# INA128.net
KiCad netlist of a schematic drawn in Altium Designer
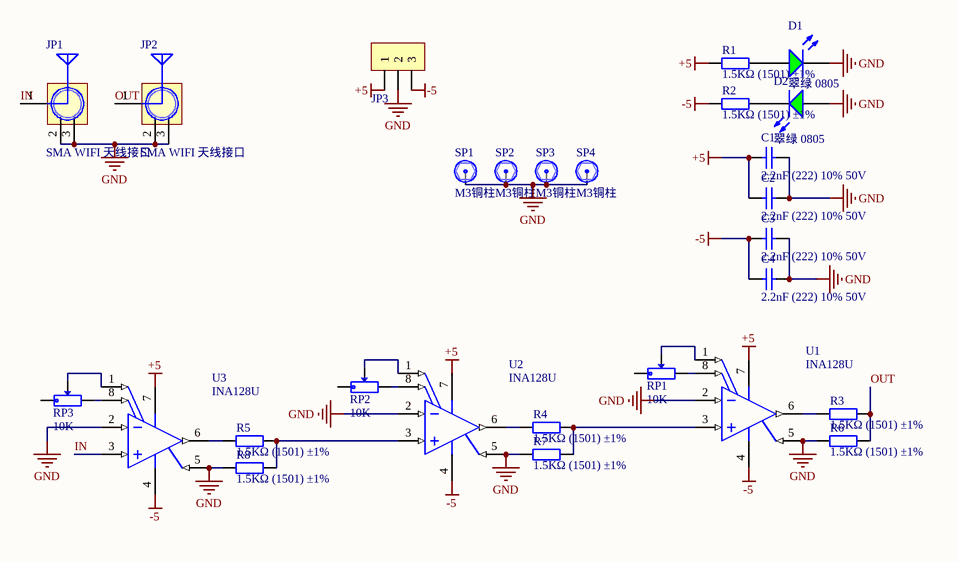
[diagram p0: INA128仪放.SchDoc]

(export (version "E")
  (design (tool "Eeschema 10.0.6"))
  (components
    (comp (ref "C1")
      (value "2.2nF (222) 10% 50V")
      (footprint "0603_C")
      (description "贴片电容")
      (libsource (lib "Miscellaneous Devices LC") (part "0603 2.2nF (222) 10% 50V"))
    )
    (comp (ref "C2")
      (value "2.2nF (222) 10% 50V")
      (footprint "0603_C")
      (description "贴片电容")
      (libsource (lib "Miscellaneous Devices LC") (part "0603 2.2nF (222) 10% 50V"))
    )
    (comp (ref "C3")
      (value "2.2nF (222) 10% 50V")
      (footprint "0603_C")
      (description "贴片电容")
      (libsource (lib "Miscellaneous Devices LC") (part "0603 2.2nF (222) 10% 50V"))
    )
    (comp (ref "C4")
      (value "2.2nF (222) 10% 50V")
      (footprint "0603_C")
      (description "贴片电容")
      (libsource (lib "Miscellaneous Devices LC") (part "0603 2.2nF (222) 10% 50V"))
    )
    (comp (ref "D1")
      (value "翠绿 0805")
      (footprint "0805_LED_S1")
      (description "发光二极管")
      (libsource (lib "Miscellaneous Devices LC") (part "0805 翠绿"))
    )
    (comp (ref "D2")
      (value "翠绿 0805")
      (footprint "0805_LED_S1")
      (description "发光二极管")
      (libsource (lib "Miscellaneous Devices LC") (part "0805 翠绿"))
    )
    (comp (ref "JP1")
      (value "SMA WIFI 天线接口")
      (footprint "SMA-KE")
      (description "SMA-2.4G射频天线接口")
      (libsource (lib "pcb_project") (part "SMA"))
    )
    (comp (ref "JP2")
      (value "SMA WIFI 天线接口")
      (footprint "SMA-KE")
      (description "SMA-2.4G射频天线接口")
      (libsource (lib "pcb_project") (part "SMA"))
    )
    (comp (ref "JP3")
      (value "HDR-1X3")
      (footprint "XH2.54-WS-3P")
      (description "3P接插件")
      (libsource (lib "pcb_project") (part "Header 3"))
    )
    (comp (ref "R1")
      (value "1.5KΩ (1501) ±1%")
      (footprint "0805_R")
      (description "贴片电阻")
      (libsource (lib "Miscellaneous Devices LC") (part "0805 1.5KΩ (1501) 1%"))
    )
    (comp (ref "R2")
      (value "1.5KΩ (1501) ±1%")
      (footprint "0805_R")
      (description "贴片电阻")
      (libsource (lib "Miscellaneous Devices LC") (part "0805 1.5KΩ (1501) 1%"))
    )
    (comp (ref "R3")
      (value "1.5KΩ (1501) ±1%")
      (footprint "0805_R")
      (description "贴片电阻")
      (libsource (lib "Miscellaneous Devices LC") (part "0805 1.5KΩ (1501) 1%"))
    )
    (comp (ref "R4")
      (value "1.5KΩ (1501) ±1%")
      (footprint "0805_R")
      (description "贴片电阻")
      (libsource (lib "Miscellaneous Devices LC") (part "0805 1.5KΩ (1501) 1%"))
    )
    (comp (ref "R5")
      (value "1.5KΩ (1501) ±1%")
      (footprint "0805_R")
      (description "贴片电阻")
      (libsource (lib "Miscellaneous Devices LC") (part "0805 1.5KΩ (1501) 1%"))
    )
    (comp (ref "R6")
      (value "1.5KΩ (1501) ±1%")
      (footprint "0805_R")
      (description "贴片电阻")
      (libsource (lib "Miscellaneous Devices LC") (part "0805 1.5KΩ (1501) 1%"))
    )
    (comp (ref "R7")
      (value "1.5KΩ (1501) ±1%")
      (footprint "0805_R")
      (description "贴片电阻")
      (libsource (lib "Miscellaneous Devices LC") (part "0805 1.5KΩ (1501) 1%"))
    )
    (comp (ref "R8")
      (value "1.5KΩ (1501) ±1%")
      (footprint "0805_R")
      (description "贴片电阻")
      (libsource (lib "Miscellaneous Devices LC") (part "0805 1.5KΩ (1501) 1%"))
    )
    (comp (ref "RP1")
      (value "10K")
      (footprint "RM065")
      (description "插件单联电位器")
      (libsource (lib "电容-电阻-电感-电位器") (part "RP-ID"))
    )
    (comp (ref "RP2")
      (value "10K")
      (footprint "RM065")
      (description "插件单联电位器")
      (libsource (lib "电容-电阻-电感-电位器") (part "RP-ID"))
    )
    (comp (ref "RP3")
      (value "10K")
      (footprint "RM065")
      (description "插件单联电位器")
      (libsource (lib "电容-电阻-电感-电位器") (part "RP-ID"))
    )
    (comp (ref "SP1")
      (value "M3铜柱")
      (footprint "M3x4_L")
      (description "铜柱")
      (libsource (lib "铜柱-测试点-电池座-蜂鸣器") (part "铜柱小焊盘"))
    )
    (comp (ref "SP2")
      (value "M3铜柱")
      (footprint "M3x4_L")
      (description "铜柱")
      (libsource (lib "铜柱-测试点-电池座-蜂鸣器") (part "铜柱小焊盘"))
    )
    (comp (ref "SP3")
      (value "M3铜柱")
      (footprint "M3x4_L")
      (description "铜柱")
      (libsource (lib "铜柱-测试点-电池座-蜂鸣器") (part "铜柱小焊盘"))
    )
    (comp (ref "SP4")
      (value "M3铜柱")
      (footprint "M3x4_L")
      (description "铜柱")
      (libsource (lib "铜柱-测试点-电池座-蜂鸣器") (part "铜柱小焊盘"))
    )
    (comp (ref "U1")
      (value "INA128U")
      (footprint "SOP8_N")
      (fields (field (name "MANUFACTURER") "Texas Instruments"))
      (libsource (lib "pcb_project") (part "CMP-0992-00017-2"))
    )
    (comp (ref "U2")
      (value "INA128U")
      (footprint "SOP8_N")
      (fields (field (name "MANUFACTURER") "Texas Instruments"))
      (libsource (lib "pcb_project") (part "CMP-0992-00017-2"))
    )
    (comp (ref "U3")
      (value "INA128U")
      (footprint "SOP8_N")
      (fields (field (name "MANUFACTURER") "Texas Instruments"))
      (libsource (lib "pcb_project") (part "CMP-0992-00017-2"))
    )
  )
  (nets
    (net (code "1") (name "+5") (class "Default")
      (node (ref "C1") (pin "1") (pinfunction "1_1") (pintype "passive"))
      (node (ref "C2") (pin "1") (pinfunction "1_1") (pintype "passive"))
      (node (ref "JP3") (pin "1") (pinfunction "1_1") (pintype "passive"))
      (node (ref "R1") (pin "1") (pinfunction "1_1") (pintype "passive"))
      (node (ref "U1") (pin "7") (pinfunction "V+_7") (pintype "power_in"))
      (node (ref "U2") (pin "7") (pinfunction "V+_7") (pintype "power_in"))
      (node (ref "U3") (pin "7") (pinfunction "V+_7") (pintype "power_in"))
    )
    (net (code "2") (name "-5") (class "Default")
      (node (ref "C3") (pin "1") (pinfunction "1_1") (pintype "passive"))
      (node (ref "C4") (pin "1") (pinfunction "1_1") (pintype "passive"))
      (node (ref "JP3") (pin "3") (pinfunction "3_3") (pintype "passive"))
      (node (ref "R2") (pin "1") (pinfunction "1_1") (pintype "passive"))
      (node (ref "U1") (pin "4") (pinfunction "V-_4") (pintype "power_in"))
      (node (ref "U2") (pin "4") (pinfunction "V-_4") (pintype "power_in"))
      (node (ref "U3") (pin "4") (pinfunction "V-_4") (pintype "power_in"))
    )
    (net (code "3") (name "/IN") (class "Default")
      (node (ref "JP1") (pin "1") (pinfunction "ANT_1") (pintype "passive"))
      (node (ref "U3") (pin "3") (pinfunction "VIN+_3") (pintype "input"))
    )
    (net (code "4") (name "/OUT") (class "Default")
      (node (ref "JP2") (pin "1") (pinfunction "ANT_1") (pintype "passive"))
      (node (ref "R3") (pin "2") (pinfunction "2_2") (pintype "passive"))
      (node (ref "R6") (pin "2") (pinfunction "2_2") (pintype "passive"))
    )
    (net (code "5") (name "GND") (class "Default")
      (node (ref "C1") (pin "2") (pinfunction "2_2") (pintype "passive"))
      (node (ref "C2") (pin "2") (pinfunction "2_2") (pintype "passive"))
      (node (ref "C3") (pin "2") (pinfunction "2_2") (pintype "passive"))
      (node (ref "C4") (pin "2") (pinfunction "2_2") (pintype "passive"))
      (node (ref "D1") (pin "K") (pinfunction "K_K") (pintype "passive"))
      (node (ref "D2") (pin "A") (pinfunction "A_A") (pintype "passive"))
      (node (ref "JP1") (pin "2") (pinfunction "GND_2") (pintype "passive"))
      (node (ref "JP1") (pin "3") (pinfunction "GND_3") (pintype "passive"))
      (node (ref "JP2") (pin "2") (pinfunction "GND_2") (pintype "passive"))
      (node (ref "JP2") (pin "3") (pinfunction "GND_3") (pintype "passive"))
      (node (ref "JP3") (pin "2") (pinfunction "2_2") (pintype "passive"))
      (node (ref "R6") (pin "1") (pinfunction "1_1") (pintype "passive"))
      (node (ref "R7") (pin "1") (pinfunction "1_1") (pintype "passive"))
      (node (ref "R8") (pin "1") (pinfunction "1_1") (pintype "passive"))
      (node (ref "SP1") (pin "1") (pinfunction "1_1") (pintype "passive"))
      (node (ref "SP2") (pin "1") (pinfunction "1_1") (pintype "passive"))
      (node (ref "SP3") (pin "1") (pinfunction "1_1") (pintype "passive"))
      (node (ref "SP4") (pin "1") (pinfunction "1_1") (pintype "passive"))
      (node (ref "U1") (pin "2") (pinfunction "VIN-_2") (pintype "input"))
      (node (ref "U1") (pin "5") (pinfunction "REF_5") (pintype "input"))
      (node (ref "U2") (pin "2") (pinfunction "VIN-_2") (pintype "input"))
      (node (ref "U2") (pin "5") (pinfunction "REF_5") (pintype "input"))
      (node (ref "U3") (pin "2") (pinfunction "VIN-_2") (pintype "input"))
      (node (ref "U3") (pin "5") (pinfunction "REF_5") (pintype "input"))
    )
    (net (code "6") (name "Net-(D1-PadA)") (class "Default")
      (node (ref "D1") (pin "A") (pinfunction "A_A") (pintype "passive"))
      (node (ref "R1") (pin "2") (pinfunction "2_2") (pintype "passive"))
    )
    (net (code "7") (name "Net-(D2-PadK)") (class "Default")
      (node (ref "D2") (pin "K") (pinfunction "K_K") (pintype "passive"))
      (node (ref "R2") (pin "2") (pinfunction "2_2") (pintype "passive"))
    )
    (net (code "8") (name "Net-(RP1-Pad2)") (class "Default")
      (node (ref "RP1") (pin "2") (pinfunction "2_2") (pintype "passive"))
      (node (ref "U1") (pin "1") (pinfunction "RG_1") (pintype "input"))
    )
    (net (code "9") (name "Net-(RP1-Pad3)") (class "Default")
      (node (ref "RP1") (pin "3") (pinfunction "3_3") (pintype "passive"))
      (node (ref "U1") (pin "8") (pinfunction "RG_8") (pintype "input"))
    )
    (net (code "10") (name "Net-(RP2-Pad2)") (class "Default")
      (node (ref "RP2") (pin "2") (pinfunction "2_2") (pintype "passive"))
      (node (ref "U2") (pin "1") (pinfunction "RG_1") (pintype "input"))
    )
    (net (code "11") (name "Net-(RP2-Pad3)") (class "Default")
      (node (ref "RP2") (pin "3") (pinfunction "3_3") (pintype "passive"))
      (node (ref "U2") (pin "8") (pinfunction "RG_8") (pintype "input"))
    )
    (net (code "12") (name "Net-(RP3-Pad2)") (class "Default")
      (node (ref "RP3") (pin "2") (pinfunction "2_2") (pintype "passive"))
      (node (ref "U3") (pin "1") (pinfunction "RG_1") (pintype "input"))
    )
    (net (code "13") (name "Net-(RP3-Pad3)") (class "Default")
      (node (ref "RP3") (pin "3") (pinfunction "3_3") (pintype "passive"))
      (node (ref "U3") (pin "8") (pinfunction "RG_8") (pintype "input"))
    )
    (net (code "14") (name "Net-(U1-VIN+)") (class "Default")
      (node (ref "R4") (pin "2") (pinfunction "2_2") (pintype "passive"))
      (node (ref "R7") (pin "2") (pinfunction "2_2") (pintype "passive"))
      (node (ref "U1") (pin "3") (pinfunction "VIN+_3") (pintype "input"))
    )
    (net (code "15") (name "Net-(U1-VO)") (class "Default")
      (node (ref "R3") (pin "1") (pinfunction "1_1") (pintype "passive"))
      (node (ref "U1") (pin "6") (pinfunction "VO_6") (pintype "output"))
    )
    (net (code "16") (name "Net-(U2-VIN+)") (class "Default")
      (node (ref "R5") (pin "2") (pinfunction "2_2") (pintype "passive"))
      (node (ref "R8") (pin "2") (pinfunction "2_2") (pintype "passive"))
      (node (ref "U2") (pin "3") (pinfunction "VIN+_3") (pintype "input"))
    )
    (net (code "17") (name "Net-(U2-VO)") (class "Default")
      (node (ref "R4") (pin "1") (pinfunction "1_1") (pintype "passive"))
      (node (ref "U2") (pin "6") (pinfunction "VO_6") (pintype "output"))
    )
    (net (code "18") (name "Net-(U3-VO)") (class "Default")
      (node (ref "R5") (pin "1") (pinfunction "1_1") (pintype "passive"))
      (node (ref "U3") (pin "6") (pinfunction "VO_6") (pintype "output"))
    )
    (net (code "19") (name "unconnected-(RP1-Pad1)") (class "Default")
      (node (ref "RP1") (pin "1") (pinfunction "1_1") (pintype "passive"))
    )
    (net (code "20") (name "unconnected-(RP2-Pad1)") (class "Default")
      (node (ref "RP2") (pin "1") (pinfunction "1_1") (pintype "passive"))
    )
    (net (code "21") (name "unconnected-(RP3-Pad1)") (class "Default")
      (node (ref "RP3") (pin "1") (pinfunction "1_1") (pintype "passive"))
    )
  )
)
